# CAN.net
KiCad netlist of a schematic drawn in Altium Designer
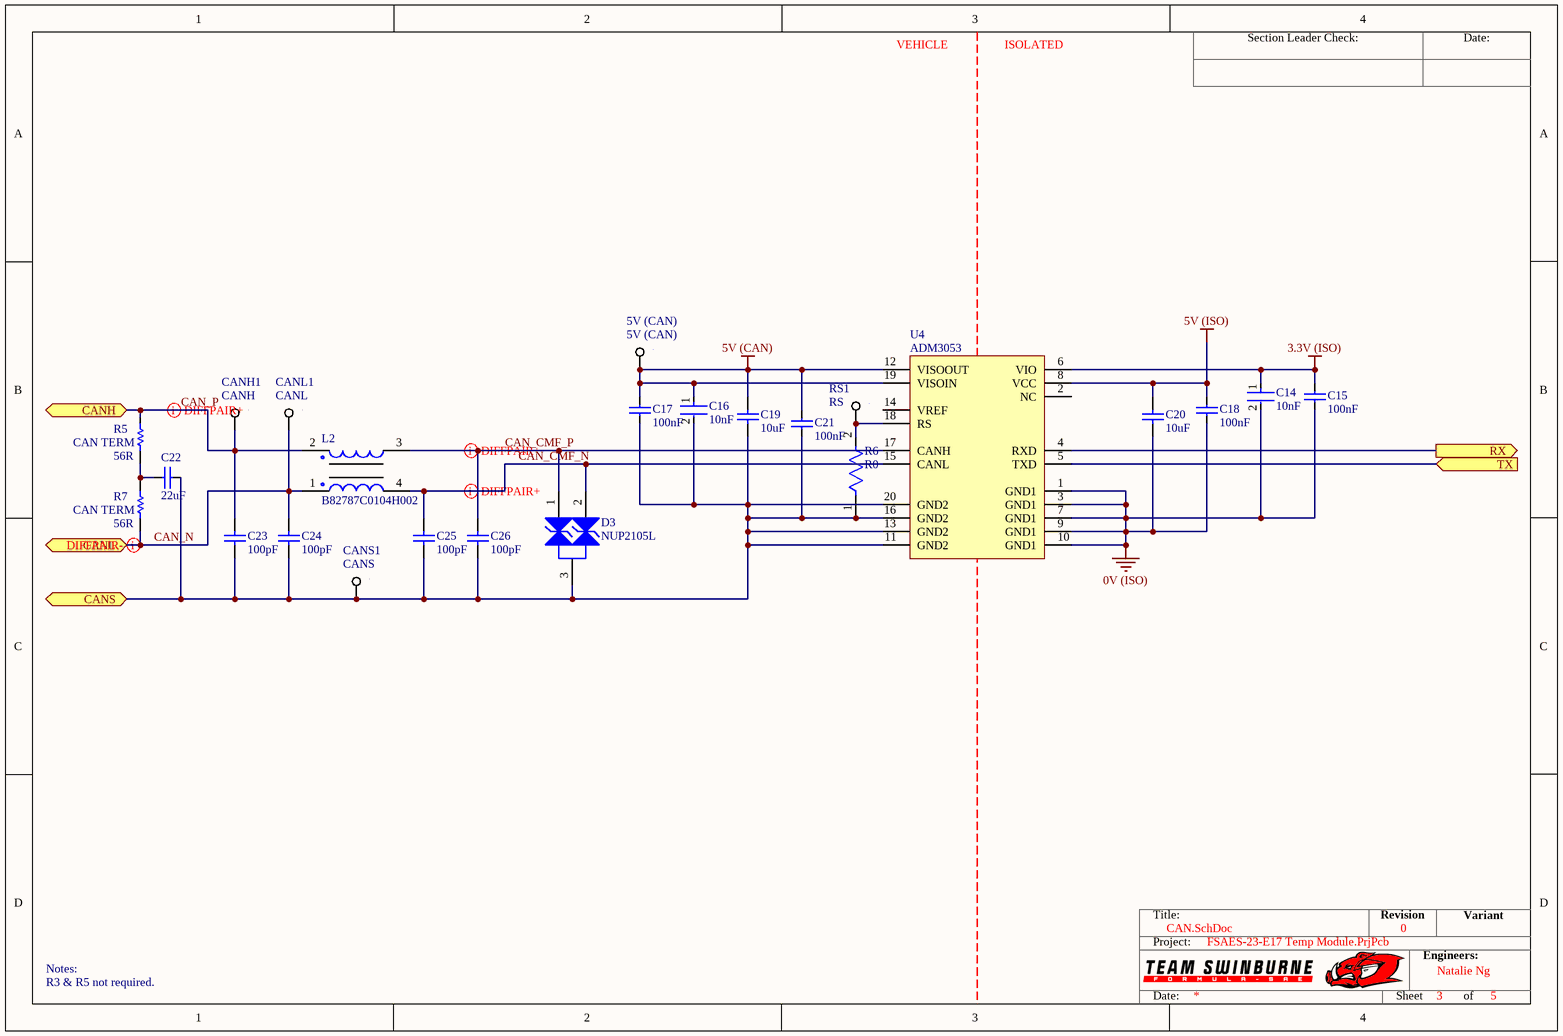
[diagram p0: CAN.SchDoc]

(export (version "E")
  (design (tool "Eeschema 10.0.6"))
  (components
    (comp (ref "5V (CAN)")
      (value "5V (CAN)")
      (footprint "SMD Test Point 1mm")
      (fields (field (name "PART NUMBER") "SMD Test Point Small") (field (name "CONTACT") "NA"))
      (libsource (lib "ts_20-standard-connectors") (part "Test Point Small"))
    )
    (comp (ref "C14")
      (value "10nF")
      (footprint "FP-GCM319-0_15-IPC_A")
      (description "CAP CER 10000PF 100V NP0 1206")
      (fields (field (name "TOLERANCE") "5%"))
      (libsource (lib "Team Swinburne") (part "b4654b650e69147ec39a6b967a45e02"))
    )
    (comp (ref "C15")
      (value "100nF")
      (footprint "0805")
      (description "Cap Ceramic 0.1uF 25V X7R 10% Pad SMD 0805 125C Automotive T/R")
      (fields (field (name "TOLERANCE") "10%"))
      (libsource (lib "Team Swinburne") (part "Capacitors"))
    )
    (comp (ref "C16")
      (value "10nF")
      (footprint "FP-GCM319-0_15-IPC_A")
      (description "CAP CER 10000PF 100V NP0 1206")
      (fields (field (name "TOLERANCE") "5%"))
      (libsource (lib "Team Swinburne") (part "b4654b650e69147ec39a6b967a45e02"))
    )
    (comp (ref "C17")
      (value "100nF")
      (footprint "0805")
      (description "Cap Ceramic 0.1uF 25V X7R 10% Pad SMD 0805 125C Automotive T/R")
      (fields (field (name "TOLERANCE") "10%"))
      (libsource (lib "Team Swinburne") (part "Capacitors"))
    )
    (comp (ref "C18")
      (value "100nF")
      (footprint "0805")
      (description "Cap Ceramic 0.1uF 25V X7R 10% Pad SMD 0805 125C Automotive T/R")
      (fields (field (name "TOLERANCE") "10%"))
      (libsource (lib "Team Swinburne") (part "Capacitors"))
    )
    (comp (ref "C19")
      (value "10uF")
      (footprint "CAPC2013X145X50NL20T25")
      (description "CAP CER 10UF 10V Y5V 0805")
      (fields (field (name "TOLERANCE") "80%"))
      (libsource (lib "Team Swinburne") (part "CAP-NP-2"))
    )
    (comp (ref "C20")
      (value "10uF")
      (footprint "CAPC2013X145X50NL20T25")
      (description "CAP CER 10UF 10V Y5V 0805")
      (fields (field (name "TOLERANCE") "80%"))
      (libsource (lib "Team Swinburne") (part "CAP-NP-2"))
    )
    (comp (ref "C21")
      (value "100nF")
      (footprint "0805")
      (description "Cap Ceramic 0.1uF 25V X7R 10% Pad SMD 0805 125C Automotive T/R")
      (fields (field (name "TOLERANCE") "10%"))
      (libsource (lib "Team Swinburne") (part "Capacitors"))
    )
    (comp (ref "C22")
      (value "22uF")
      (footprint "C0805C226M9PAC7210-Footprint-1")
      (description "Cap Ceramic 22uF 6.3V X5R 20% Pad SMD 0805 85C T/R")
      (fields (field (name "TOLERANCE") "20%"))
      (libsource (lib "Team Swinburne") (part "C0805C226M9PAC7210-Symbol-1"))
    )
    (comp (ref "C23")
      (value "100pF")
      (footprint "CAPC2013X70X45NL15T25")
      (description "Cap Ceramic 100pF 50V C0G 5% Pad SMD 0805 125C Automotive T/R")
      (fields (field (name "TOLERANCE") "5%"))
      (libsource (lib "Team Swinburne") (part "CAP"))
    )
    (comp (ref "C24")
      (value "100pF")
      (footprint "CAPC2013X70X45NL15T25")
      (description "Cap Ceramic 100pF 50V C0G 5% Pad SMD 0805 125C Automotive T/R")
      (fields (field (name "TOLERANCE") "5%"))
      (libsource (lib "Team Swinburne") (part "CAP"))
    )
    (comp (ref "C25")
      (value "100pF")
      (footprint "CAPC2013X70X45NL15T25")
      (description "Cap Ceramic 100pF 50V C0G 5% Pad SMD 0805 125C Automotive T/R")
      (fields (field (name "TOLERANCE") "5%"))
      (libsource (lib "Team Swinburne") (part "CAP"))
    )
    (comp (ref "C26")
      (value "100pF")
      (footprint "CAPC2013X70X45NL15T25")
      (description "Cap Ceramic 100pF 50V C0G 5% Pad SMD 0805 125C Automotive T/R")
      (fields (field (name "TOLERANCE") "5%"))
      (libsource (lib "Team Swinburne") (part "CAP"))
    )
    (comp (ref "CANH1")
      (value "CANH")
      (footprint "SMD Test Point 1mm")
      (fields (field (name "PART NUMBER") "SMD Test Point Small") (field (name "CONTACT") "NA"))
      (libsource (lib "ts_20-standard-connectors") (part "Test Point Small"))
    )
    (comp (ref "CANL1")
      (value "CANL")
      (footprint "SMD Test Point 1mm")
      (fields (field (name "PART NUMBER") "SMD Test Point Small") (field (name "CONTACT") "NA"))
      (libsource (lib "ts_20-standard-connectors") (part "Test Point Small"))
    )
    (comp (ref "CANS1")
      (value "CANS")
      (footprint "SMD Test Point 1mm")
      (fields (field (name "PART NUMBER") "SMD Test Point Small") (field (name "CONTACT") "NA"))
      (libsource (lib "ts_20-standard-connectors") (part "Test Point Small"))
    )
    (comp (ref "D3")
      (value "NUP2105L")
      (footprint "ONSC-SOT-23-3-318-08_V")
      (description "NUP2105L Series 350 W Dual Line CAN Bus Protector ESD Protection Diode - SOT-23")
      (libsource (lib "Team Swinburne") (part "ONSC-NUP21X5X-SOT-23-3-318-08"))
    )
    (comp (ref "L2")
      (value "B82787C0104H002")
      (footprint "TDK 4-PC Pad")
      (description "100µH @ 100kHz 2 Line Common Mode Choke Surface Mount 5.8 kOhms @ 10MHz 150mA DCR 2Ohm")
      (fields
        (field (name "MANUFACTURER") "EPCOS (TDK)")
        (field (name "DIGIKEY PART NUMBER") "495-4598-1-ND")
      )
      (libsource (lib "ts_20-standard-library") (part "B82787C0104H002"))
    )
    (comp (ref "R5")
      (value "CAN TERM")
      (footprint "RESC0603")
      (description "RES SMD 56 OHM JUMPER 1/10W 0603")
      (fields (field (name "ALTIUM_VALUE") "56R") (field (name "TOLERANCE") "1%"))
      (libsource (lib "Team Swinburne") (part "Resistor"))
    )
    (comp (ref "R6")
      (value "R0")
      (footprint "FP-RC0805-IPC_A")
      (description "Res Thick Film 0805 0 Ohm Epoxy Pad SMD T/R")
      (fields (field (name "TOLERANCE") "1%"))
      (libsource (lib "Team Swinburne") (part "1029c3af85768c4190bb7ad29bc67b5"))
    )
    (comp (ref "R7")
      (value "CAN TERM")
      (footprint "RESC0603")
      (description "RES SMD 56 OHM JUMPER 1/10W 0603")
      (fields (field (name "ALTIUM_VALUE") "56R") (field (name "TOLERANCE") "1%"))
      (libsource (lib "Team Swinburne") (part "Resistor"))
    )
    (comp (ref "RS1")
      (value "RS")
      (footprint "SMD Test Point 1mm")
      (fields (field (name "PART NUMBER") "SMD Test Point Small") (field (name "CONTACT") "NA"))
      (libsource (lib "ts_20-standard-connectors") (part "Test Point Small"))
    )
    (comp (ref "U4")
      (value "ADM3053")
      (footprint "AD SOIC-W 20")
      (description "Isolated CAN Transceiver")
      (fields
        (field (name "MANUFACTURER") "Analogue Devices")
        (field (name "DIGIKEY PART NUMBER") "ADM3053BRWZ-ND")
      )
      (libsource (lib "ts_20-standard-library") (part "ADM3053"))
    )
  )
  (nets
    (net (code "1") (name "/CANS") (class "Default")
      (node (ref "C16") (pin "2") (pinfunction "2_2") (pintype "passive"))
      (node (ref "C17") (pin "2") (pinfunction "2_2") (pintype "passive"))
      (node (ref "C19") (pin "1") (pinfunction "1_1") (pintype "passive"))
      (node (ref "C21") (pin "2") (pinfunction "2_2") (pintype "passive"))
      (node (ref "C22") (pin "2") (pinfunction "2_2") (pintype "passive"))
      (node (ref "C23") (pin "1") (pinfunction "1_1") (pintype "passive"))
      (node (ref "C24") (pin "1") (pinfunction "1_1") (pintype "passive"))
      (node (ref "C25") (pin "1") (pinfunction "1_1") (pintype "passive"))
      (node (ref "C26") (pin "1") (pinfunction "1_1") (pintype "passive"))
      (node (ref "CANS1") (pin "1") (pinfunction "1_1") (pintype "passive"))
      (node (ref "D3") (pin "3") (pinfunction "K_3") (pintype "passive"))
      (node (ref "R6") (pin "1") (pinfunction "1_1") (pintype "passive"))
      (node (ref "U4") (pin "11") (pinfunction "GND2_11") (pintype "passive"))
      (node (ref "U4") (pin "13") (pinfunction "GND2_13") (pintype "passive"))
      (node (ref "U4") (pin "16") (pinfunction "GND2_16") (pintype "passive"))
      (node (ref "U4") (pin "20") (pinfunction "GND2_20") (pintype "passive"))
    )
    (net (code "2") (name "/CAN_CMF_N") (class "Default")
      (node (ref "C25") (pin "2") (pinfunction "2_2") (pintype "passive"))
      (node (ref "D3") (pin "2") (pinfunction "K_2") (pintype "passive"))
      (node (ref "L2") (pin "4") (pinfunction "4_4") (pintype "passive"))
      (node (ref "U4") (pin "15") (pinfunction "CANL_15") (pintype "passive"))
    )
    (net (code "3") (name "/CAN_CMF_P") (class "Default")
      (node (ref "C26") (pin "2") (pinfunction "2_2") (pintype "passive"))
      (node (ref "D3") (pin "1") (pinfunction "K_1") (pintype "passive"))
      (node (ref "L2") (pin "3") (pinfunction "3_3") (pintype "power_in"))
      (node (ref "U4") (pin "17") (pinfunction "CANH_17") (pintype "passive"))
    )
    (net (code "4") (name "/CAN_N") (class "Default")
      (node (ref "C24") (pin "2") (pinfunction "2_2") (pintype "passive"))
      (node (ref "CANL1") (pin "1") (pinfunction "1_1") (pintype "passive"))
      (node (ref "L2") (pin "1") (pinfunction "1_1") (pintype "passive"))
      (node (ref "R7") (pin "1") (pinfunction "1_1") (pintype "passive"))
    )
    (net (code "5") (name "/CAN_P") (class "Default")
      (node (ref "C23") (pin "2") (pinfunction "2_2") (pintype "passive"))
      (node (ref "CANH1") (pin "1") (pinfunction "1_1") (pintype "passive"))
      (node (ref "L2") (pin "2") (pinfunction "2_2") (pintype "passive"))
      (node (ref "R5") (pin "2") (pinfunction "2_2") (pintype "passive"))
    )
    (net (code "6") (name "/RX") (class "Default")
      (node (ref "U4") (pin "4") (pinfunction "RXD_4") (pintype "passive"))
    )
    (net (code "7") (name "/TX") (class "Default")
      (node (ref "U4") (pin "5") (pinfunction "TXD_5") (pintype "passive"))
    )
    (net (code "8") (name "0V (ISO)") (class "Default")
      (node (ref "C14") (pin "2") (pinfunction "2_2") (pintype "passive"))
      (node (ref "C15") (pin "2") (pinfunction "2_2") (pintype "passive"))
      (node (ref "C18") (pin "2") (pinfunction "2_2") (pintype "passive"))
      (node (ref "C20") (pin "1") (pinfunction "1_1") (pintype "passive"))
      (node (ref "U4") (pin "1") (pinfunction "GND1_1") (pintype "passive"))
      (node (ref "U4") (pin "10") (pinfunction "GND1_10") (pintype "passive"))
      (node (ref "U4") (pin "3") (pinfunction "GND1_3") (pintype "passive"))
      (node (ref "U4") (pin "7") (pinfunction "GND1_7") (pintype "passive"))
      (node (ref "U4") (pin "9") (pinfunction "GND1_9") (pintype "passive"))
    )
    (net (code "9") (name "3.3V (ISO)") (class "Default")
      (node (ref "C14") (pin "1") (pinfunction "1_1") (pintype "passive"))
      (node (ref "C15") (pin "1") (pinfunction "1_1") (pintype "passive"))
      (node (ref "U4") (pin "6") (pinfunction "VIO_6") (pintype "passive"))
    )
    (net (code "10") (name "5V (CAN)") (class "Default")
      (node (ref "5V (CAN)") (pin "1") (pinfunction "1_1") (pintype "passive"))
      (node (ref "C16") (pin "1") (pinfunction "1_1") (pintype "passive"))
      (node (ref "C17") (pin "1") (pinfunction "1_1") (pintype "passive"))
      (node (ref "C19") (pin "2") (pinfunction "2_2") (pintype "passive"))
      (node (ref "C21") (pin "1") (pinfunction "1_1") (pintype "passive"))
      (node (ref "U4") (pin "12") (pinfunction "VISOOUT_12") (pintype "passive"))
      (node (ref "U4") (pin "19") (pinfunction "VISOIN_19") (pintype "passive"))
    )
    (net (code "11") (name "5V (ISO)") (class "Default")
      (node (ref "C18") (pin "1") (pinfunction "1_1") (pintype "passive"))
      (node (ref "C20") (pin "2") (pinfunction "2_2") (pintype "passive"))
      (node (ref "U4") (pin "8") (pinfunction "VCC_8") (pintype "passive"))
    )
    (net (code "12") (name "Net-(C22-Pad1)") (class "Default")
      (node (ref "C22") (pin "1") (pinfunction "1_1") (pintype "passive"))
      (node (ref "R5") (pin "1") (pinfunction "1_1") (pintype "passive"))
      (node (ref "R7") (pin "2") (pinfunction "2_2") (pintype "passive"))
    )
    (net (code "13") (name "Net-(U4-RS)") (class "Default")
      (node (ref "R6") (pin "2") (pinfunction "2_2") (pintype "passive"))
      (node (ref "RS1") (pin "1") (pinfunction "1_1") (pintype "passive"))
      (node (ref "U4") (pin "18") (pinfunction "RS_18") (pintype "passive"))
    )
    (net (code "14") (name "unconnected-(U4-NC-Pad2)") (class "Default")
      (node (ref "U4") (pin "2") (pinfunction "NC_2") (pintype "passive"))
    )
    (net (code "15") (name "unconnected-(U4-VREF-Pad14)") (class "Default")
      (node (ref "U4") (pin "14") (pinfunction "VREF_14") (pintype "passive"))
    )
  )
)
